# v13.net
KiCad netlist of a schematic drawn in EAGLE
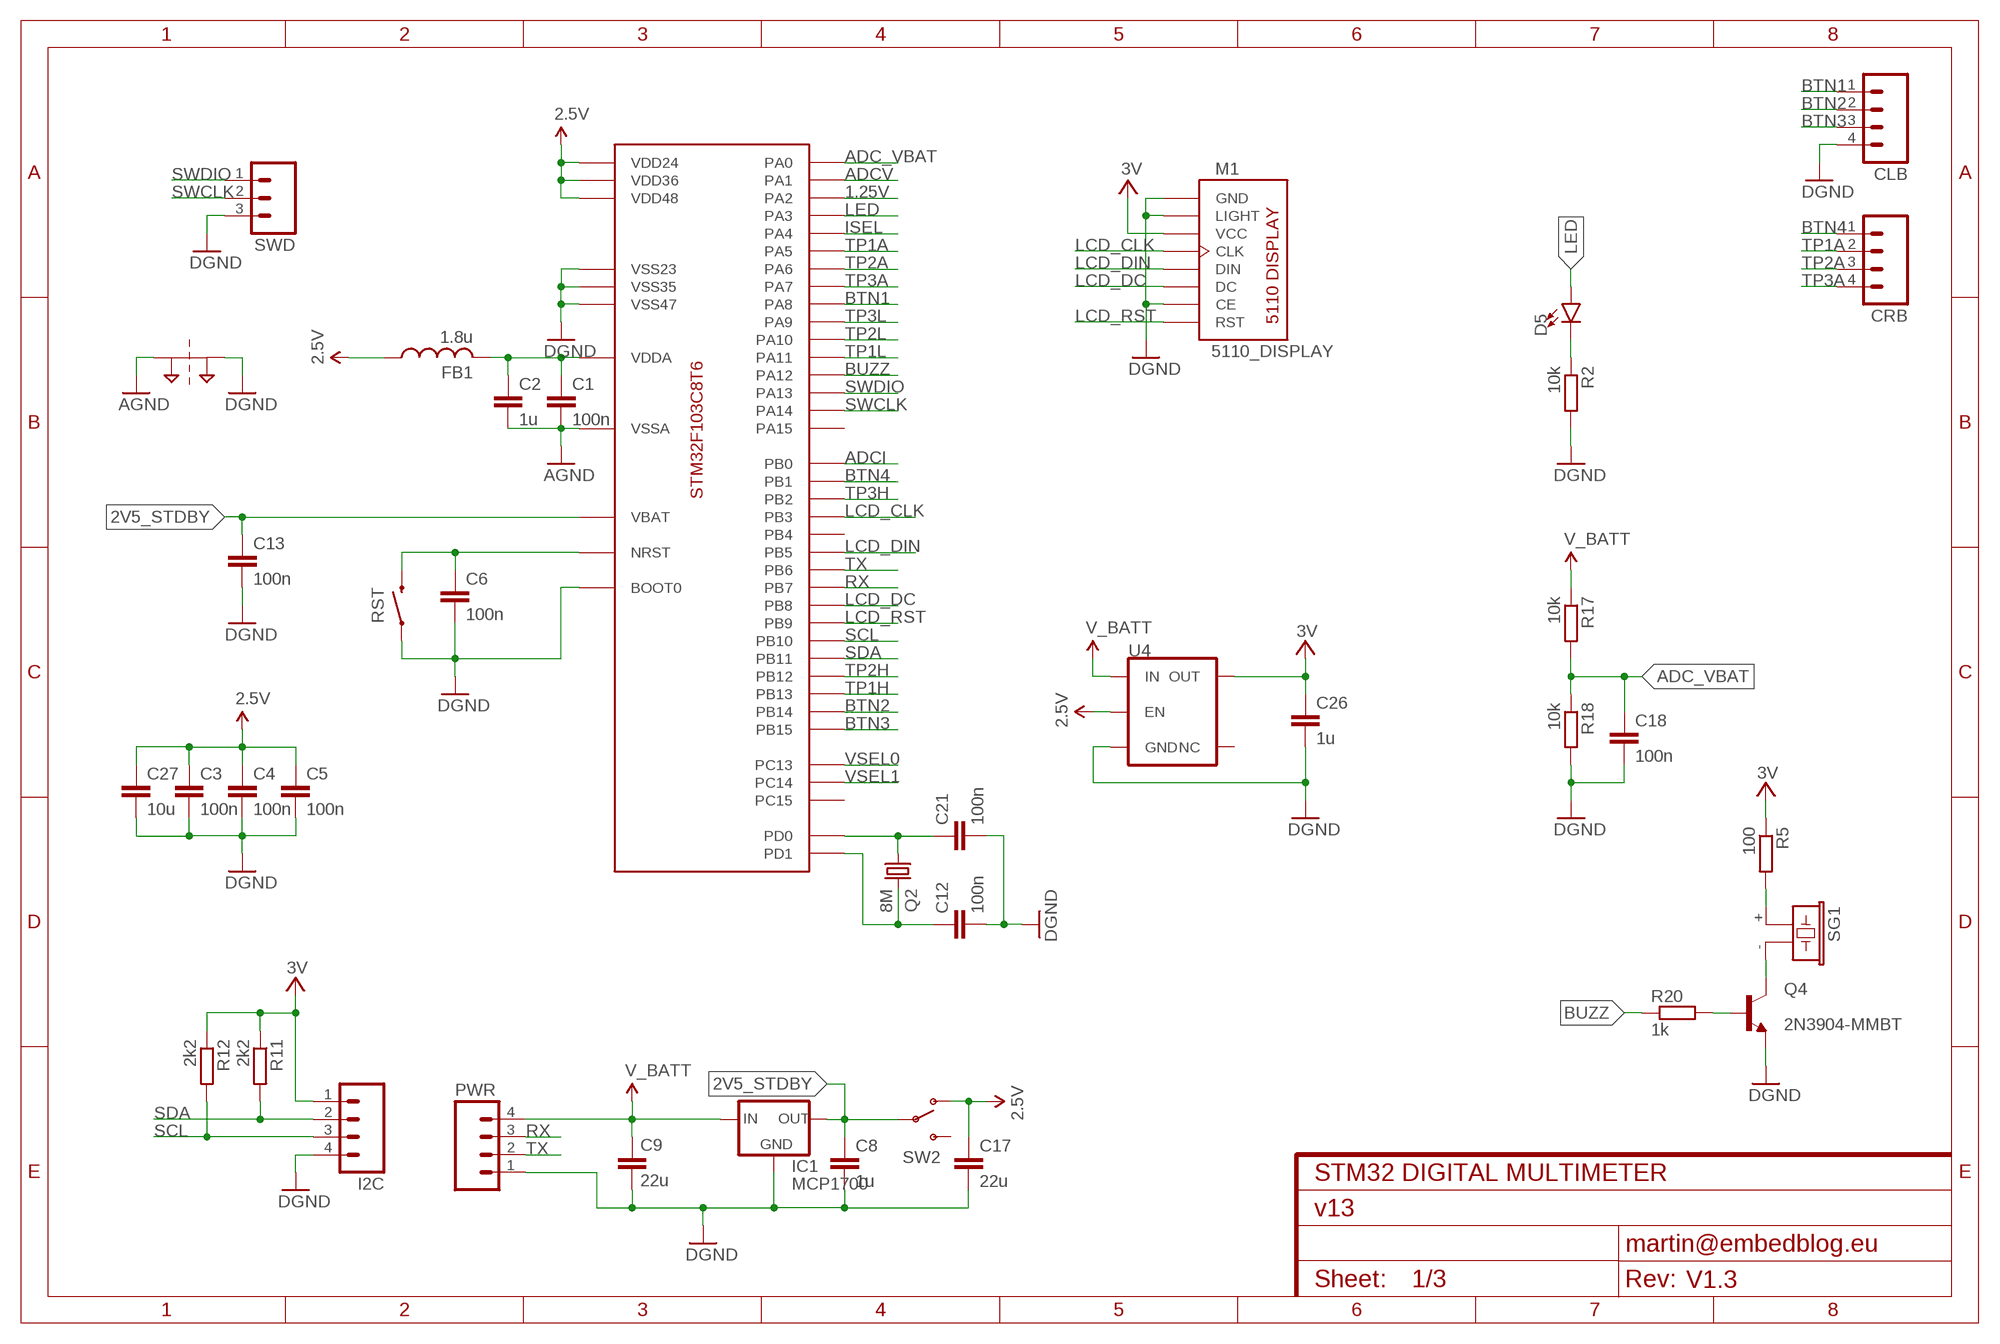
[diagram p0: schematic, sheet 1]
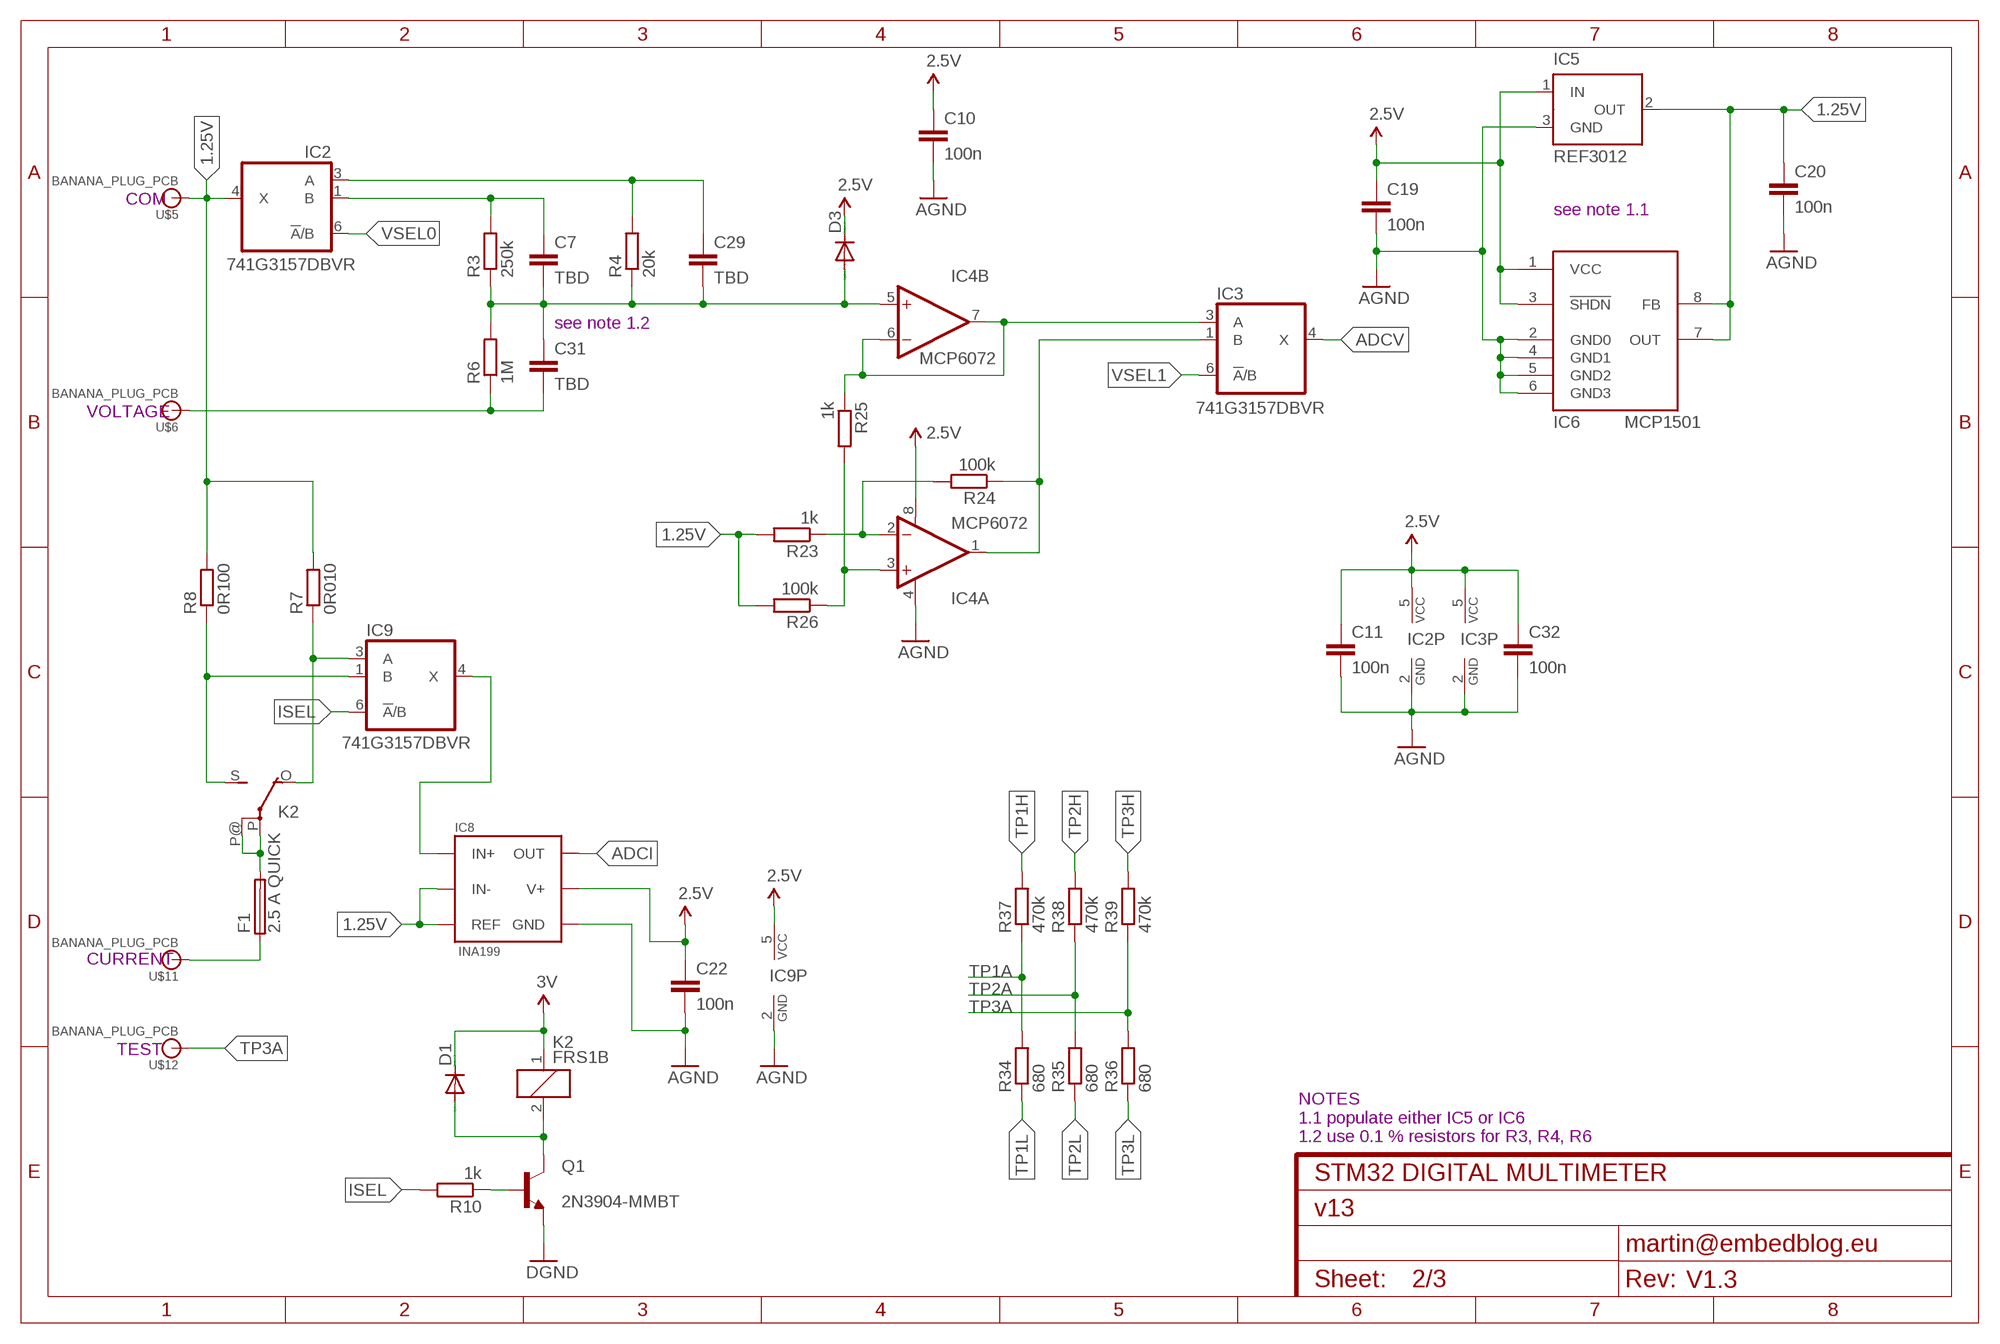
[diagram p1: schematic, sheet 2]
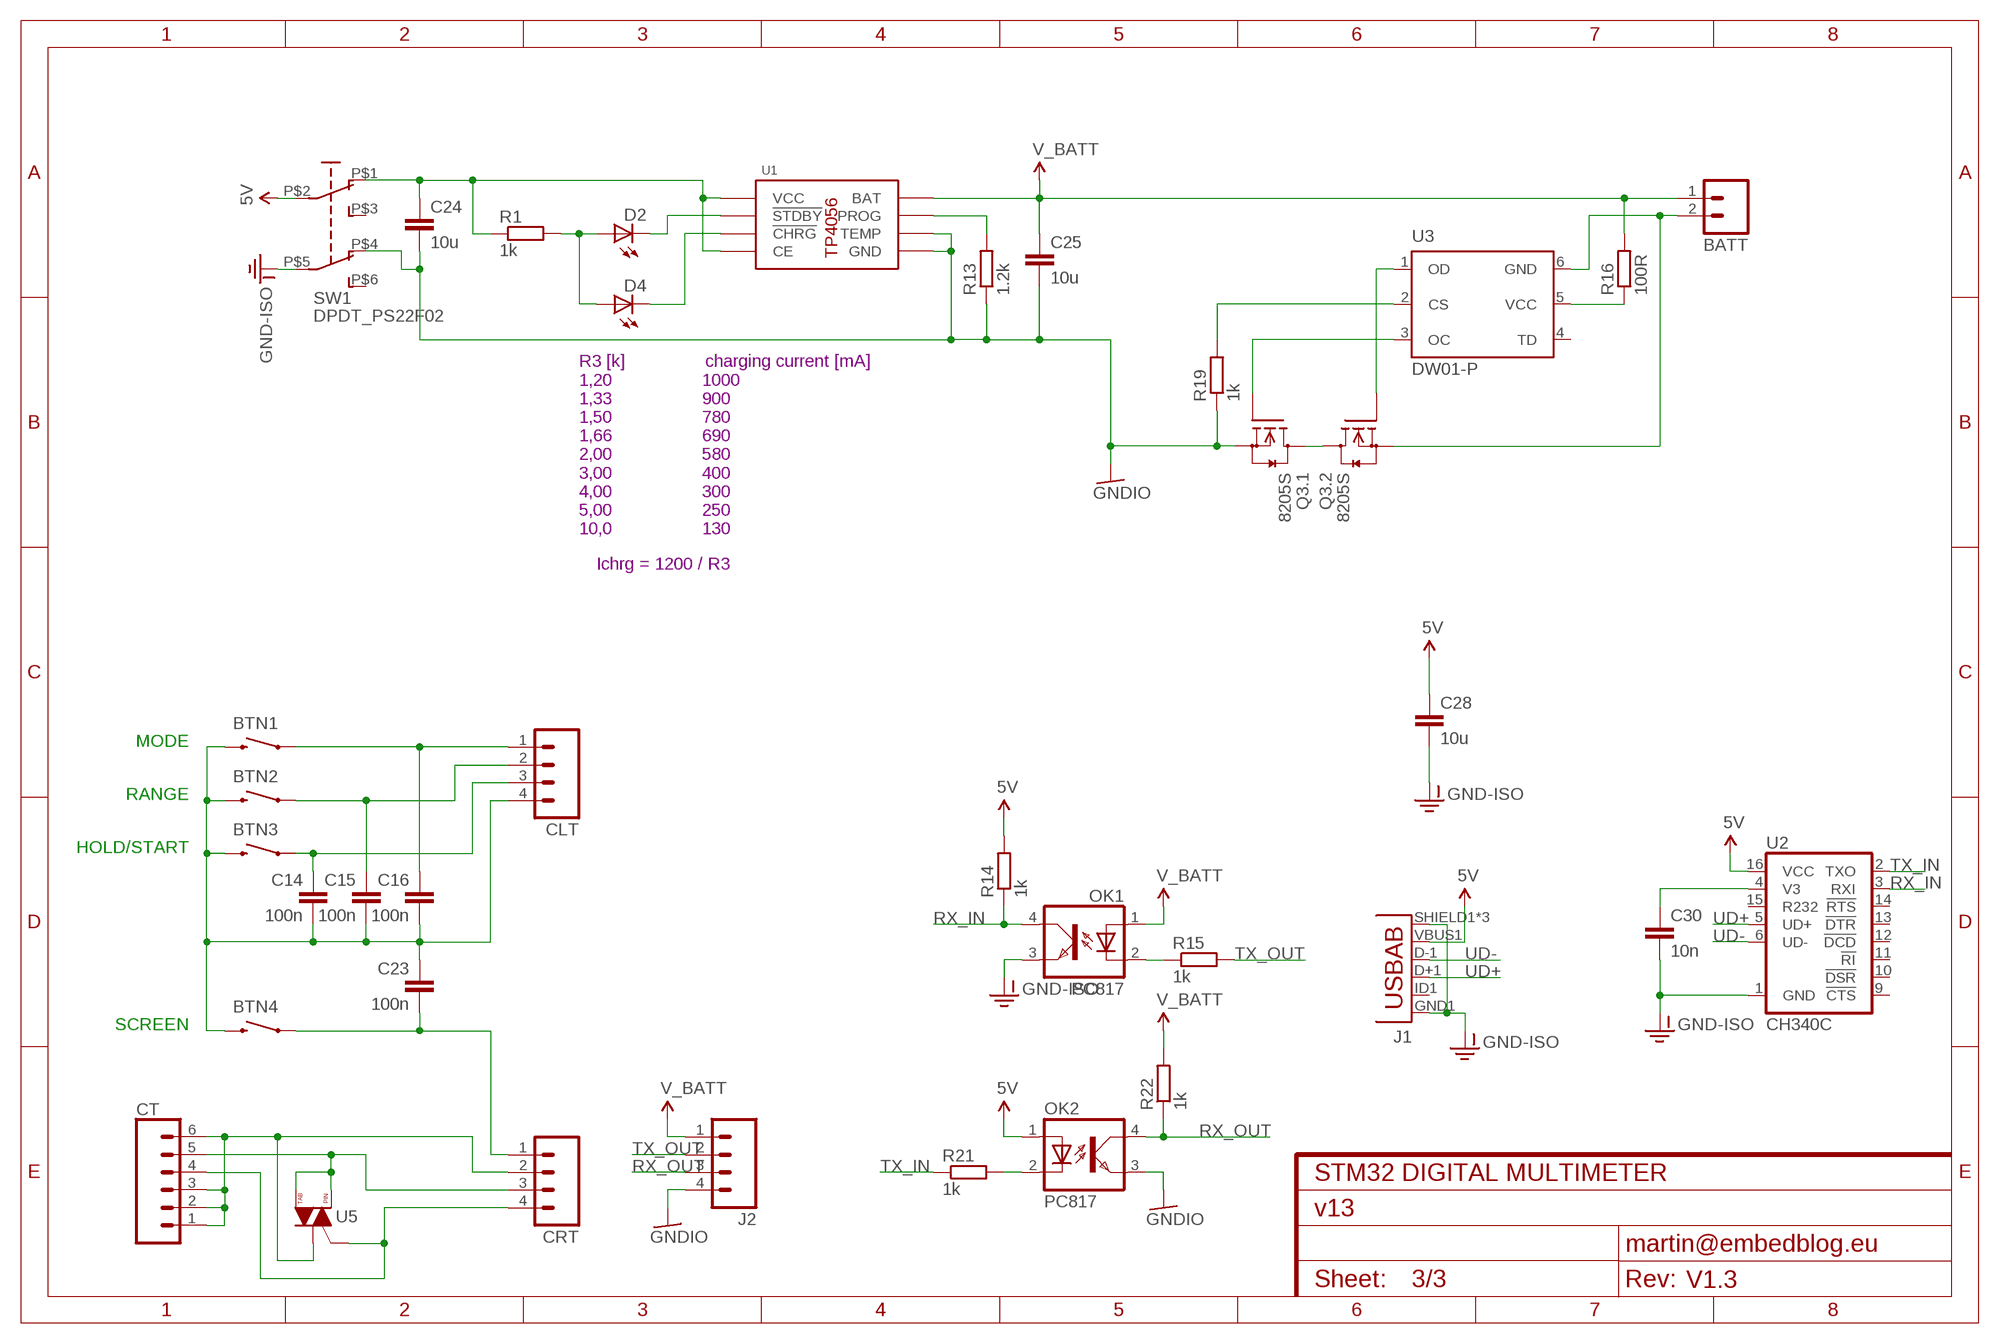
[diagram p2: schematic, sheet 3]

(export (version "E")
  (design (tool "Eeschema 10.0.6"))
  (components
    (comp (ref "C7")
      (value "TBD")
      (footprint "eagle-import:1206")
      (libsource (lib "eagle-import") (part "CAP1206"))
    )
    (comp (ref "C10")
      (value "100n")
      (footprint "eagle-import:1206")
      (libsource (lib "eagle-import") (part "CAP1206"))
    )
    (comp (ref "C11")
      (value "100n")
      (footprint "eagle-import:1206")
      (libsource (lib "eagle-import") (part "CAP1206"))
    )
    (comp (ref "C19")
      (value "100n")
      (footprint "eagle-import:C1206")
      (libsource (lib "eagle-import") (part "C-EUC1206"))
    )
    (comp (ref "C20")
      (value "100n")
      (footprint "eagle-import:C1206")
      (libsource (lib "eagle-import") (part "C-EUC1206"))
    )
    (comp (ref "C22")
      (value "100n")
      (footprint "eagle-import:1206")
      (libsource (lib "eagle-import") (part "CAP1206"))
    )
    (comp (ref "C29")
      (value "TBD")
      (footprint "eagle-import:1206")
      (libsource (lib "eagle-import") (part "CAP1206"))
    )
    (comp (ref "C31")
      (value "TBD")
      (footprint "eagle-import:1206")
      (libsource (lib "eagle-import") (part "CAP1206"))
    )
    (comp (ref "C32")
      (value "100n")
      (footprint "eagle-import:1206")
      (libsource (lib "eagle-import") (part "CAP1206"))
    )
    (comp (ref "D1")
      (value "DIODE-MINIMELF")
      (footprint "eagle-import:MINIMELF")
      (libsource (lib "eagle-import") (part "DIODE-MINIMELF"))
    )
    (comp (ref "D3")
      (value "DIODE-MINIMELF")
      (footprint "eagle-import:MINIMELF")
      (libsource (lib "eagle-import") (part "DIODE-MINIMELF"))
    )
    (comp (ref "F1")
      (value "2.5 A QUICK")
      (footprint "eagle-import:SHK20L")
      (libsource (lib "eagle-import") (part "FUSESHK20L"))
    )
    (comp (ref "IC2")
      (value "741G3157DBVR")
      (footprint "eagle-import:DBV_R-PDSO-G6")
      (libsource (lib "eagle-import") (part "741G3157DBVR"))
    )
    (comp (ref "IC3")
      (value "741G3157DBVR")
      (footprint "eagle-import:DBV_R-PDSO-G6")
      (libsource (lib "eagle-import") (part "741G3157DBVR"))
    )
    (comp (ref "IC4")
      (value "MCP6072")
      (footprint "eagle-import:SO08")
      (libsource (lib "eagle-import") (part "OPAMP-DUALU"))
    )
    (comp (ref "IC5")
      (value "REF3012")
      (footprint "eagle-import:SOT23")
      (fields (field (name "MF") "MAXIM") (field (name "MPN") "MAX6520EUR-T"))
      (libsource (lib "eagle-import") (part "MAX6520"))
    )
    (comp (ref "IC6")
      (value "MCP1501")
      (footprint "eagle-import:SO08")
      (libsource (lib "eagle-import") (part "MCP1501"))
    )
    (comp (ref "IC8")
      (value "INA199")
      (footprint "eagle-import:SC70-6")
      (libsource (lib "eagle-import") (part "INA199"))
    )
    (comp (ref "IC9")
      (value "741G3157DBVR")
      (footprint "eagle-import:DBV_R-PDSO-G6")
      (libsource (lib "eagle-import") (part "741G3157DBVR"))
    )
    (comp (ref "K2")
      (value "FRS1B")
      (footprint "eagle-import:FRS1B")
      (libsource (lib "eagle-import") (part "FRS1B"))
    )
    (comp (ref "Q1")
      (value "2N3904-MMBT")
      (footprint "eagle-import:SOT23")
      (libsource (lib "eagle-import") (part "2N3904-MMBT"))
    )
    (comp (ref "R3")
      (value "250k")
      (footprint "eagle-import:R1206")
      (libsource (lib "eagle-import") (part "R-EU_R1206"))
    )
    (comp (ref "R4")
      (value "20k")
      (footprint "eagle-import:R1206")
      (libsource (lib "eagle-import") (part "R-EU_R1206"))
    )
    (comp (ref "R6")
      (value "1M")
      (footprint "eagle-import:R1206")
      (libsource (lib "eagle-import") (part "R-EU_R1206"))
    )
    (comp (ref "R7")
      (value "0R010")
      (footprint "eagle-import:R1206")
      (libsource (lib "eagle-import") (part "R-EU_R1206"))
    )
    (comp (ref "R8")
      (value "0R100")
      (footprint "eagle-import:R1206")
      (libsource (lib "eagle-import") (part "R-EU_R1206"))
    )
    (comp (ref "R10")
      (value "1k")
      (footprint "eagle-import:R1206")
      (libsource (lib "eagle-import") (part "R-EU_R1206"))
    )
    (comp (ref "R23")
      (value "1k")
      (footprint "eagle-import:R1206")
      (libsource (lib "eagle-import") (part "R-EU_R1206"))
    )
    (comp (ref "R24")
      (value "100k")
      (footprint "eagle-import:R1206")
      (libsource (lib "eagle-import") (part "R-EU_R1206"))
    )
    (comp (ref "R25")
      (value "1k")
      (footprint "eagle-import:R1206")
      (libsource (lib "eagle-import") (part "R-EU_R1206"))
    )
    (comp (ref "R26")
      (value "100k")
      (footprint "eagle-import:R1206")
      (libsource (lib "eagle-import") (part "R-EU_R1206"))
    )
    (comp (ref "R34")
      (value "680")
      (footprint "eagle-import:R1206")
      (libsource (lib "eagle-import") (part "R-EU_R1206"))
    )
    (comp (ref "R35")
      (value "680")
      (footprint "eagle-import:R1206")
      (libsource (lib "eagle-import") (part "R-EU_R1206"))
    )
    (comp (ref "R36")
      (value "680")
      (footprint "eagle-import:R1206")
      (libsource (lib "eagle-import") (part "R-EU_R1206"))
    )
    (comp (ref "R37")
      (value "470k")
      (footprint "eagle-import:R1206")
      (libsource (lib "eagle-import") (part "R-EU_R1206"))
    )
    (comp (ref "R38")
      (value "470k")
      (footprint "eagle-import:R1206")
      (libsource (lib "eagle-import") (part "R-EU_R1206"))
    )
    (comp (ref "R39")
      (value "470k")
      (footprint "eagle-import:R1206")
      (libsource (lib "eagle-import") (part "R-EU_R1206"))
    )
    (comp (ref "U$5")
      (value "BANANA_PLUG_PCB")
      (footprint "eagle-import:BANANA_6MMHOLE")
      (libsource (lib "eagle-import") (part "BANANA_PLUG_PCB"))
    )
    (comp (ref "U$6")
      (value "BANANA_PLUG_PCB")
      (footprint "eagle-import:BANANA_6MMHOLE")
      (libsource (lib "eagle-import") (part "BANANA_PLUG_PCB"))
    )
    (comp (ref "U$11")
      (value "BANANA_PLUG_PCB")
      (footprint "eagle-import:BANANA_6MMHOLE")
      (libsource (lib "eagle-import") (part "BANANA_PLUG_PCB"))
    )
    (comp (ref "U$12")
      (value "BANANA_PLUG_PCB")
      (footprint "eagle-import:BANANA_6MMHOLE")
      (libsource (lib "eagle-import") (part "BANANA_PLUG_PCB"))
    )
    (comp (ref "BATT")
      (value "M02PTH3")
      (footprint "eagle-import:1X02_LONGPADS")
      (libsource (lib "eagle-import") (part "M02PTH3"))
    )
    (comp (ref "BTN1")
      (value "SWITCH-MOMENTARY-2PTH")
      (footprint "eagle-import:TACTILE-PTH")
      (libsource (lib "eagle-import") (part "SWITCH-MOMENTARY-2PTH"))
    )
    (comp (ref "BTN2")
      (value "SWITCH-MOMENTARY-2PTH")
      (footprint "eagle-import:TACTILE-PTH")
      (libsource (lib "eagle-import") (part "SWITCH-MOMENTARY-2PTH"))
    )
    (comp (ref "BTN3")
      (value "SWITCH-MOMENTARY-2PTH")
      (footprint "eagle-import:TACTILE-PTH")
      (libsource (lib "eagle-import") (part "SWITCH-MOMENTARY-2PTH"))
    )
    (comp (ref "BTN4")
      (value "SWITCH-MOMENTARY-2PTH")
      (footprint "eagle-import:TACTILE-PTH")
      (libsource (lib "eagle-import") (part "SWITCH-MOMENTARY-2PTH"))
    )
    (comp (ref "C14")
      (value "100n")
      (footprint "eagle-import:C1206")
      (libsource (lib "eagle-import") (part "C-EUC1206"))
    )
    (comp (ref "C15")
      (value "100n")
      (footprint "eagle-import:C1206")
      (libsource (lib "eagle-import") (part "C-EUC1206"))
    )
    (comp (ref "C16")
      (value "100n")
      (footprint "eagle-import:C1206")
      (libsource (lib "eagle-import") (part "C-EUC1206"))
    )
    (comp (ref "C23")
      (value "100n")
      (footprint "eagle-import:C1206")
      (libsource (lib "eagle-import") (part "C-EUC1206"))
    )
    (comp (ref "C24")
      (value "10u")
      (footprint "eagle-import:C1206")
      (libsource (lib "eagle-import") (part "C-EUC1206"))
    )
    (comp (ref "C25")
      (value "10u")
      (footprint "eagle-import:C1206")
      (libsource (lib "eagle-import") (part "C-EUC1206"))
    )
    (comp (ref "C28")
      (value "10u")
      (footprint "eagle-import:C1206")
      (libsource (lib "eagle-import") (part "C-EUC1206"))
    )
    (comp (ref "C30")
      (value "10n")
      (footprint "eagle-import:C1206")
      (libsource (lib "eagle-import") (part "C-EUC1206"))
    )
    (comp (ref "CLT")
      (value "M04PTH")
      (footprint "eagle-import:1X04@1")
      (libsource (lib "eagle-import") (part "M04PTH"))
    )
    (comp (ref "CRT")
      (value "M04PTH")
      (footprint "eagle-import:1X04@1")
      (libsource (lib "eagle-import") (part "M04PTH"))
    )
    (comp (ref "CT")
      (value "CONN_06NO_SILK_FEMALE_PTH")
      (footprint "eagle-import:1X06_NO_SILK")
      (libsource (lib "eagle-import") (part "CONN_06NO_SILK_FEMALE_PTH"))
    )
    (comp (ref "D2")
      (value "LEDCHIPLED_1206")
      (footprint "eagle-import:CHIPLED_1206")
      (libsource (lib "eagle-import") (part "LEDCHIPLED_1206"))
    )
    (comp (ref "D4")
      (value "LEDCHIPLED_1206")
      (footprint "eagle-import:CHIPLED_1206")
      (libsource (lib "eagle-import") (part "LEDCHIPLED_1206"))
    )
    (comp (ref "J1")
      (value "USB-ABCONN-11794")
      (footprint "eagle-import:USB-AB-MICRO-SMD_V03")
      (libsource (lib "eagle-import") (part "USB-ABCONN-11794"))
    )
    (comp (ref "J2")
      (value "M04PTH")
      (footprint "eagle-import:1X04@1")
      (libsource (lib "eagle-import") (part "M04PTH"))
    )
    (comp (ref "OK1")
      (value "PC817")
      (footprint "eagle-import:DIL04")
      (fields (field (name "MPN") "PC817X4J000F"))
      (libsource (lib "eagle-import") (part "PC817"))
    )
    (comp (ref "OK2")
      (value "PC817")
      (footprint "eagle-import:DIL04")
      (fields (field (name "MPN") "PC817X4J000F"))
      (libsource (lib "eagle-import") (part "PC817"))
    )
    (comp (ref "Q3")
      (value "8205S")
      (footprint "eagle-import:SSOT-6")
      (libsource (lib "eagle-import") (part "FDC6305N"))
    )
    (comp (ref "R1")
      (value "1k")
      (footprint "eagle-import:R1206")
      (libsource (lib "eagle-import") (part "R-EU_R1206"))
    )
    (comp (ref "R13")
      (value "1.2k")
      (footprint "eagle-import:R1206")
      (libsource (lib "eagle-import") (part "R-EU_R1206"))
    )
    (comp (ref "R14")
      (value "1k")
      (footprint "eagle-import:R1206")
      (libsource (lib "eagle-import") (part "R-EU_R1206"))
    )
    (comp (ref "R15")
      (value "1k")
      (footprint "eagle-import:R1206")
      (libsource (lib "eagle-import") (part "R-EU_R1206"))
    )
    (comp (ref "R16")
      (value "100R")
      (footprint "eagle-import:R1206")
      (libsource (lib "eagle-import") (part "R-EU_R1206"))
    )
    (comp (ref "R19")
      (value "1k")
      (footprint "eagle-import:R1206")
      (libsource (lib "eagle-import") (part "R-EU_R1206"))
    )
    (comp (ref "R21")
      (value "1k")
      (footprint "eagle-import:R1206")
      (libsource (lib "eagle-import") (part "R-EU_R1206"))
    )
    (comp (ref "R22")
      (value "1k")
      (footprint "eagle-import:R1206")
      (libsource (lib "eagle-import") (part "R-EU_R1206"))
    )
    (comp (ref "SW1")
      (value "DPDT_PS22F02")
      (footprint "eagle-import:PS22_L02_DPDT_SW")
      (libsource (lib "eagle-import") (part "DPDT_PS22F02"))
    )
    (comp (ref "U1")
      (value "TP4056")
      (footprint "eagle-import:SOP8")
      (libsource (lib "eagle-import") (part "TP4056"))
    )
    (comp (ref "U2")
      (value "CH340C")
      (footprint "eagle-import:SO016")
      (libsource (lib "eagle-import") (part "CH340C"))
    )
    (comp (ref "U3")
      (value "DW01-P")
      (footprint "eagle-import:SOT23-6L")
      (libsource (lib "eagle-import") (part "DW01-P"))
    )
    (comp (ref "U5")
      (value "TRIAC-HPSMD")
      (footprint "eagle-import:SOT223")
      (libsource (lib "eagle-import") (part "TRIAC-HPSMD"))
    )
    (comp (ref "C1")
      (value "100n")
      (footprint "eagle-import:C1206")
      (libsource (lib "eagle-import") (part "C-EUC1206"))
    )
    (comp (ref "C2")
      (value "1u")
      (footprint "eagle-import:C1206")
      (libsource (lib "eagle-import") (part "C-EUC1206"))
    )
    (comp (ref "C3")
      (value "100n")
      (footprint "eagle-import:C1206")
      (libsource (lib "eagle-import") (part "C-EUC1206"))
    )
    (comp (ref "C4")
      (value "100n")
      (footprint "eagle-import:C1206")
      (libsource (lib "eagle-import") (part "C-EUC1206"))
    )
    (comp (ref "C5")
      (value "100n")
      (footprint "eagle-import:C1206")
      (libsource (lib "eagle-import") (part "C-EUC1206"))
    )
    (comp (ref "C6")
      (value "100n")
      (footprint "eagle-import:C1206")
      (libsource (lib "eagle-import") (part "C-EUC1206"))
    )
    (comp (ref "C8")
      (value "1u")
      (footprint "eagle-import:C1206")
      (libsource (lib "eagle-import") (part "C-EUC1206"))
    )
    (comp (ref "C9")
      (value "22u")
      (footprint "eagle-import:C1206")
      (libsource (lib "eagle-import") (part "C-EUC1206"))
    )
    (comp (ref "C12")
      (value "100n")
      (footprint "eagle-import:C1206")
      (libsource (lib "eagle-import") (part "C-EUC1206"))
    )
    (comp (ref "C13")
      (value "100n")
      (footprint "eagle-import:C1206")
      (libsource (lib "eagle-import") (part "C-EUC1206"))
    )
    (comp (ref "C17")
      (value "22u")
      (footprint "eagle-import:C1206")
      (libsource (lib "eagle-import") (part "C-EUC1206"))
    )
    (comp (ref "C18")
      (value "100n")
      (footprint "eagle-import:C1206")
      (libsource (lib "eagle-import") (part "C-EUC1206"))
    )
    (comp (ref "C21")
      (value "100n")
      (footprint "eagle-import:C1206")
      (libsource (lib "eagle-import") (part "C-EUC1206"))
    )
    (comp (ref "C26")
      (value "1u")
      (footprint "eagle-import:C1206")
      (libsource (lib "eagle-import") (part "C-EUC1206"))
    )
    (comp (ref "C27")
      (value "10u")
      (footprint "eagle-import:C1206")
      (libsource (lib "eagle-import") (part "C-EUC1206"))
    )
    (comp (ref "CLB")
      (value "M04PTH")
      (footprint "eagle-import:1X04@1")
      (libsource (lib "eagle-import") (part "M04PTH"))
    )
    (comp (ref "CRB")
      (value "M04PTH")
      (footprint "eagle-import:1X04@1")
      (libsource (lib "eagle-import") (part "M04PTH"))
    )
    (comp (ref "D5")
      (value "LED1206")
      (footprint "eagle-import:LED-1206")
      (libsource (lib "eagle-import") (part "LED1206"))
    )
    (comp (ref "FB1")
      (value "1.8u")
      (footprint "eagle-import:1206")
      (libsource (lib "eagle-import") (part "FERRITE-BEADC"))
    )
    (comp (ref "I2C")
      (value "M04PTH")
      (footprint "eagle-import:1X04@1")
      (libsource (lib "eagle-import") (part "M04PTH"))
    )
    (comp (ref "IC1")
      (value "MCP1700")
      (footprint "eagle-import:SOT23")
      (libsource (lib "eagle-import") (part "XC63FPM"))
    )
    (comp (ref "M1")
      (value "5110_DISPLAY")
      (footprint "eagle-import:5110_LAYOUT")
      (libsource (lib "eagle-import") (part "5110_DISPLAY"))
    )
    (comp (ref "PWR")
      (value "M04PTH")
      (footprint "eagle-import:1X04@1")
      (libsource (lib "eagle-import") (part "M04PTH"))
    )
    (comp (ref "Q2")
      (value "8M")
      (footprint "eagle-import:HC49U-V")
      (libsource (lib "eagle-import") (part "CRYSTALHC49U-V"))
    )
    (comp (ref "Q4")
      (value "2N3904-MMBT")
      (footprint "eagle-import:SOT23")
      (libsource (lib "eagle-import") (part "2N3904-MMBT"))
    )
    (comp (ref "R2")
      (value "10k")
      (footprint "eagle-import:R1206")
      (libsource (lib "eagle-import") (part "R-EU_R1206"))
    )
    (comp (ref "R5")
      (value "100")
      (footprint "eagle-import:R1206")
      (libsource (lib "eagle-import") (part "R-EU_R1206"))
    )
    (comp (ref "R11")
      (value "2k2")
      (footprint "eagle-import:R1206")
      (libsource (lib "eagle-import") (part "R-EU_R1206"))
    )
    (comp (ref "R12")
      (value "2k2")
      (footprint "eagle-import:R1206")
      (libsource (lib "eagle-import") (part "R-EU_R1206"))
    )
    (comp (ref "R17")
      (value "10k")
      (footprint "eagle-import:R1206")
      (libsource (lib "eagle-import") (part "R-EU_R1206"))
    )
    (comp (ref "R18")
      (value "10k")
      (footprint "eagle-import:R1206")
      (libsource (lib "eagle-import") (part "R-EU_R1206"))
    )
    (comp (ref "R20")
      (value "1k")
      (footprint "eagle-import:R1206")
      (libsource (lib "eagle-import") (part "R-EU_R1206"))
    )
    (comp (ref "RST")
      (value "SWITCH-MOMENTARY-2SMD")
      (footprint "eagle-import:TACTILE-SWITCH-SMD")
      (libsource (lib "eagle-import") (part "SWITCH-MOMENTARY-2SMD"))
    )
    (comp (ref "SG1")
      (value "F/CM12P")
      (footprint "eagle-import:F_CM12P")
      (libsource (lib "eagle-import") (part "F/CM12P"))
    )
    (comp (ref "SJ1")
      (value "2PT_GND_TIE")
      (footprint "eagle-import:2PT_GND_TIE")
      (libsource (lib "eagle-import") (part "2PT_GND_TIE"))
    )
    (comp (ref "SW2")
      (value "SK-12D07")
      (footprint "eagle-import:SK12SWITCH")
      (libsource (lib "eagle-import") (part "SK-12D07"))
    )
    (comp (ref "SWD")
      (value "M03PTH")
      (footprint "eagle-import:1X03")
      (libsource (lib "eagle-import") (part "M03PTH"))
    )
    (comp (ref "U$1")
      (value "STM32F103C8T6")
      (footprint "eagle-import:TQFP-48")
      (libsource (lib "eagle-import") (part "STM32F103C8T6"))
    )
    (comp (ref "U4")
      (value "3.3V")
      (footprint "eagle-import:SOT23-5")
      (libsource (lib "eagle-import") (part "V_REG_AP2112K-3.3V"))
    )
  )
  (nets
    (net (code "1") (name "1.25V") (class "Default")
      (node (ref "C20") (pin "1") (pinfunction "1_1") (pintype "passive"))
      (node (ref "IC2") (pin "4") (pinfunction "X_4") (pintype "bidirectional"))
      (node (ref "IC5") (pin "2") (pinfunction "OUT_2") (pintype "output"))
      (node (ref "IC6") (pin "7") (pinfunction "OUT_7") (pintype "bidirectional"))
      (node (ref "IC6") (pin "8") (pinfunction "FB_8") (pintype "bidirectional"))
      (node (ref "IC8") (pin "1") (pinfunction "REF_1") (pintype "bidirectional"))
      (node (ref "IC8") (pin "5") (pinfunction "IN-_5") (pintype "bidirectional"))
      (node (ref "R23") (pin "2") (pinfunction "2_2") (pintype "passive"))
      (node (ref "R26") (pin "2") (pinfunction "2_2") (pintype "passive"))
      (node (ref "R7") (pin "2") (pinfunction "2_2") (pintype "passive"))
      (node (ref "R8") (pin "2") (pinfunction "2_2") (pintype "passive"))
      (node (ref "U$1") (pin "12") (pinfunction "PA2_12") (pintype "bidirectional"))
      (node (ref "U$5") (pin "P$1") (pinfunction "1_P$1") (pintype "passive"))
    )
    (net (code "2") (name "2.5V") (class "Default")
      (node (ref "C10") (pin "1") (pinfunction "1_1") (pintype "passive"))
      (node (ref "C11") (pin "1") (pinfunction "1_1") (pintype "passive"))
      (node (ref "C17") (pin "1") (pinfunction "1_1") (pintype "passive"))
      (node (ref "C19") (pin "1") (pinfunction "1_1") (pintype "passive"))
      (node (ref "C22") (pin "1") (pinfunction "1_1") (pintype "passive"))
      (node (ref "C27") (pin "1") (pinfunction "1_1") (pintype "passive"))
      (node (ref "C3") (pin "1") (pinfunction "1_1") (pintype "passive"))
      (node (ref "C32") (pin "1") (pinfunction "1_1") (pintype "passive"))
      (node (ref "C4") (pin "1") (pinfunction "1_1") (pintype "passive"))
      (node (ref "C5") (pin "1") (pinfunction "1_1") (pintype "passive"))
      (node (ref "D3") (pin "C") (pinfunction "C_C") (pintype "passive"))
      (node (ref "FB1") (pin "1") (pinfunction "1_1") (pintype "passive"))
      (node (ref "IC2") (pin "5") (pinfunction "VCC_5") (pintype "power_in"))
      (node (ref "IC3") (pin "5") (pinfunction "VCC_5") (pintype "power_in"))
      (node (ref "IC4") (pin "8") (pinfunction "V+_8") (pintype "power_in"))
      (node (ref "IC5") (pin "1") (pinfunction "IN_1") (pintype "input"))
      (node (ref "IC6") (pin "1") (pinfunction "VCC_1") (pintype "bidirectional"))
      (node (ref "IC6") (pin "3") (pinfunction "~{SHDN}_3") (pintype "bidirectional"))
      (node (ref "IC8") (pin "3") (pinfunction "V+_3") (pintype "bidirectional"))
      (node (ref "IC9") (pin "5") (pinfunction "VCC_5") (pintype "power_in"))
      (node (ref "SW2") (pin "IN") (pinfunction "O_IN") (pintype "passive"))
      (node (ref "U$1") (pin "24") (pinfunction "VDD24_24") (pintype "input"))
      (node (ref "U$1") (pin "36") (pinfunction "VDD36_36") (pintype "input"))
      (node (ref "U$1") (pin "48") (pinfunction "VDD48_48") (pintype "input"))
      (node (ref "U4") (pin "3") (pinfunction "EN_3") (pintype "input"))
    )
    (net (code "3") (name "2V5_STDBY") (class "Default")
      (node (ref "C13") (pin "1") (pinfunction "1_1") (pintype "passive"))
      (node (ref "C8") (pin "1") (pinfunction "1_1") (pintype "passive"))
      (node (ref "IC1") (pin "2") (pinfunction "OUT_2") (pintype "passive"))
      (node (ref "SW2") (pin "P1") (pinfunction "P_P1") (pintype "passive"))
      (node (ref "U$1") (pin "1") (pinfunction "VBAT_1") (pintype "input"))
    )
    (net (code "4") (name "3V") (class "Default")
      (node (ref "C26") (pin "1") (pinfunction "1_1") (pintype "passive"))
      (node (ref "D1") (pin "C") (pinfunction "C_C") (pintype "passive"))
      (node (ref "I2C") (pin "1") (pinfunction "1_1") (pintype "passive"))
      (node (ref "K2") (pin "1") (pinfunction "1_1") (pintype "passive"))
      (node (ref "M1") (pin "VCC") (pinfunction "VCC_VCC") (pintype "bidirectional"))
      (node (ref "R11") (pin "1") (pinfunction "1_1") (pintype "passive"))
      (node (ref "R12") (pin "1") (pinfunction "1_1") (pintype "passive"))
      (node (ref "R5") (pin "1") (pinfunction "1_1") (pintype "passive"))
      (node (ref "U4") (pin "5") (pinfunction "OUT_5") (pintype "passive"))
    )
    (net (code "5") (name "5V") (class "Default")
      (node (ref "C28") (pin "1") (pinfunction "1_1") (pintype "passive"))
      (node (ref "J1") (pin "VBUS1") (pinfunction "VBUS_VBUS1") (pintype "bidirectional"))
      (node (ref "OK2") (pin "1") (pinfunction "A_1") (pintype "passive"))
      (node (ref "R14") (pin "2") (pinfunction "2_2") (pintype "passive"))
      (node (ref "SW1") (pin "P$2") (pinfunction "P_P$2") (pintype "passive"))
      (node (ref "U2") (pin "16") (pinfunction "VCC_16") (pintype "bidirectional"))
    )
    (net (code "6") (name "ADCI") (class "Default")
      (node (ref "IC8") (pin "6") (pinfunction "OUT_6") (pintype "bidirectional"))
      (node (ref "U$1") (pin "18") (pinfunction "PB0_18") (pintype "bidirectional"))
    )
    (net (code "7") (name "ADCV") (class "Default")
      (node (ref "IC3") (pin "4") (pinfunction "X_4") (pintype "bidirectional"))
      (node (ref "U$1") (pin "11") (pinfunction "PA1_11") (pintype "bidirectional"))
    )
    (net (code "8") (name "ADC_VBAT") (class "Default")
      (node (ref "C18") (pin "1") (pinfunction "1_1") (pintype "passive"))
      (node (ref "R17") (pin "2") (pinfunction "2_2") (pintype "passive"))
      (node (ref "R18") (pin "1") (pinfunction "1_1") (pintype "passive"))
      (node (ref "U$1") (pin "10") (pinfunction "PA0_10") (pintype "bidirectional"))
    )
    (net (code "9") (name "AGND") (class "Default")
      (node (ref "C1") (pin "2") (pinfunction "2_2") (pintype "passive"))
      (node (ref "C10") (pin "2") (pinfunction "2_2") (pintype "passive"))
      (node (ref "C11") (pin "2") (pinfunction "2_2") (pintype "passive"))
      (node (ref "C19") (pin "2") (pinfunction "2_2") (pintype "passive"))
      (node (ref "C2") (pin "2") (pinfunction "2_2") (pintype "passive"))
      (node (ref "C20") (pin "2") (pinfunction "2_2") (pintype "passive"))
      (node (ref "C22") (pin "2") (pinfunction "2_2") (pintype "passive"))
      (node (ref "C32") (pin "2") (pinfunction "2_2") (pintype "passive"))
      (node (ref "IC2") (pin "2") (pinfunction "GND_2") (pintype "power_in"))
      (node (ref "IC3") (pin "2") (pinfunction "GND_2") (pintype "power_in"))
      (node (ref "IC4") (pin "4") (pinfunction "V-_4") (pintype "power_in"))
      (node (ref "IC5") (pin "3") (pinfunction "GND_3") (pintype "power_in"))
      (node (ref "IC6") (pin "2") (pinfunction "GND0_2") (pintype "bidirectional"))
      (node (ref "IC6") (pin "4") (pinfunction "GND1_4") (pintype "bidirectional"))
      (node (ref "IC6") (pin "5") (pinfunction "GND2_5") (pintype "bidirectional"))
      (node (ref "IC6") (pin "6") (pinfunction "GND3_6") (pintype "bidirectional"))
      (node (ref "IC8") (pin "2") (pinfunction "GND_2") (pintype "bidirectional"))
      (node (ref "IC9") (pin "2") (pinfunction "GND_2") (pintype "power_in"))
      (node (ref "SJ1") (pin "P$1") (pinfunction "P$1_P$1") (pintype "bidirectional"))
      (node (ref "U$1") (pin "8") (pinfunction "VSSA_8") (pintype "input"))
    )
    (net (code "10") (name "BTN1") (class "Default")
      (node (ref "CLB") (pin "1") (pinfunction "1_1") (pintype "passive"))
      (node (ref "U$1") (pin "29") (pinfunction "PA8_29") (pintype "bidirectional"))
    )
    (net (code "11") (name "BTN2") (class "Default")
      (node (ref "CLB") (pin "2") (pinfunction "2_2") (pintype "passive"))
      (node (ref "U$1") (pin "27") (pinfunction "PB14_27") (pintype "bidirectional"))
    )
    (net (code "12") (name "BTN3") (class "Default")
      (node (ref "CLB") (pin "3") (pinfunction "3_3") (pintype "passive"))
      (node (ref "U$1") (pin "28") (pinfunction "PB15_28") (pintype "bidirectional"))
    )
    (net (code "13") (name "BTN4") (class "Default")
      (node (ref "CRB") (pin "1") (pinfunction "1_1") (pintype "passive"))
      (node (ref "U$1") (pin "19") (pinfunction "PB1_19") (pintype "bidirectional"))
    )
    (net (code "14") (name "BUZZ") (class "Default")
      (node (ref "R20") (pin "1") (pinfunction "1_1") (pintype "passive"))
      (node (ref "U$1") (pin "33") (pinfunction "PA12_33") (pintype "bidirectional"))
    )
    (net (code "15") (name "GND") (class "Default")
      (node (ref "C12") (pin "2") (pinfunction "2_2") (pintype "passive"))
      (node (ref "C13") (pin "2") (pinfunction "2_2") (pintype "passive"))
      (node (ref "C17") (pin "2") (pinfunction "2_2") (pintype "passive"))
      (node (ref "C18") (pin "2") (pinfunction "2_2") (pintype "passive"))
      (node (ref "C21") (pin "2") (pinfunction "2_2") (pintype "passive"))
      (node (ref "C26") (pin "2") (pinfunction "2_2") (pintype "passive"))
      (node (ref "C27") (pin "2") (pinfunction "2_2") (pintype "passive"))
      (node (ref "C3") (pin "2") (pinfunction "2_2") (pintype "passive"))
      (node (ref "C4") (pin "2") (pinfunction "2_2") (pintype "passive"))
      (node (ref "C5") (pin "2") (pinfunction "2_2") (pintype "passive"))
      (node (ref "C6") (pin "2") (pinfunction "2_2") (pintype "passive"))
      (node (ref "C8") (pin "2") (pinfunction "2_2") (pintype "passive"))
      (node (ref "C9") (pin "2") (pinfunction "2_2") (pintype "passive"))
      (node (ref "CLB") (pin "4") (pinfunction "4_4") (pintype "passive"))
      (node (ref "I2C") (pin "4") (pinfunction "4_4") (pintype "passive"))
      (node (ref "IC1") (pin "1") (pinfunction "GND_1") (pintype "input"))
      (node (ref "M1") (pin "CE") (pinfunction "CE_CE") (pintype "bidirectional"))
      (node (ref "M1") (pin "GND") (pinfunction "GND_GND") (pintype "bidirectional"))
      (node (ref "M1") (pin "LIGHT") (pinfunction "LIGHT_LIGHT") (pintype "bidirectional"))
      (node (ref "PWR") (pin "1") (pinfunction "1_1") (pintype "passive"))
      (node (ref "Q1") (pin "2") (pinfunction "E_2") (pintype "passive"))
      (node (ref "Q4") (pin "2") (pinfunction "E_2") (pintype "passive"))
      (node (ref "R18") (pin "2") (pinfunction "2_2") (pintype "passive"))
      (node (ref "R2") (pin "2") (pinfunction "2_2") (pintype "passive"))
      (node (ref "RST") (pin "1") (pinfunction "1_1") (pintype "passive"))
      (node (ref "SJ1") (pin "P$2") (pinfunction "P$2_P$2") (pintype "bidirectional"))
      (node (ref "SWD") (pin "3") (pinfunction "3_3") (pintype "passive"))
      (node (ref "U$1") (pin "23") (pinfunction "VSS23_23") (pintype "input"))
      (node (ref "U$1") (pin "35") (pinfunction "VSS35_35") (pintype "input"))
      (node (ref "U$1") (pin "44") (pinfunction "BOOT0_44") (pintype "input"))
      (node (ref "U$1") (pin "47") (pinfunction "VSS47_47") (pintype "input"))
      (node (ref "U4") (pin "2") (pinfunction "GND_2") (pintype "input"))
    )
    (net (code "16") (name "GND-ISO") (class "Default")
      (node (ref "C28") (pin "2") (pinfunction "2_2") (pintype "passive"))
      (node (ref "C30") (pin "2") (pinfunction "2_2") (pintype "passive"))
      (node (ref "J1") (pin "GND1") (pinfunction "GND_GND1") (pintype "bidirectional"))
      (node (ref "J1") (pin "SHIELD1") (pinfunction "SHIELD_SHIELD1") (pintype "bidirectional"))
      (node (ref "J1") (pin "SHIELD2") (pinfunction "SHIELD_SHIELD2") (pintype "bidirectional"))
      (node (ref "J1") (pin "SHIELD3") (pinfunction "SHIELD_SHIELD3") (pintype "bidirectional"))
      (node (ref "OK1") (pin "3") (pinfunction "EMIT_3") (pintype "passive"))
      (node (ref "SW1") (pin "P$5") (pinfunction "P1_P$5") (pintype "passive"))
      (node (ref "U2") (pin "1") (pinfunction "GND_1") (pintype "bidirectional"))
    )
    (net (code "17") (name "GNDIO") (class "Default")
      (node (ref "C24") (pin "2") (pinfunction "2_2") (pintype "passive"))
      (node (ref "C25") (pin "2") (pinfunction "2_2") (pintype "passive"))
      (node (ref "J2") (pin "4") (pinfunction "4_4") (pintype "passive"))
      (node (ref "OK2") (pin "3") (pinfunction "EMIT_3") (pintype "passive"))
      (node (ref "Q3") (pin "5") (pinfunction "S_5") (pintype "passive"))
      (node (ref "R13") (pin "1") (pinfunction "1_1") (pintype "passive"))
      (node (ref "R19") (pin "1") (pinfunction "1_1") (pintype "passive"))
      (node (ref "SW1") (pin "P$4") (pinfunction "O1_P$4") (pintype "passive"))
      (node (ref "U1") (pin "1") (pinfunction "TEMP_1") (pintype "bidirectional"))
      (node (ref "U1") (pin "3") (pinfunction "GND_3") (pintype "bidirectional"))
    )
    (net (code "18") (name "ISEL") (class "Default")
      (node (ref "IC9") (pin "6") (pinfunction "~{A}/B_6") (pintype "input"))
      (node (ref "R10") (pin "2") (pinfunction "2_2") (pintype "passive"))
      (node (ref "U$1") (pin "14") (pinfunction "PA4_14") (pintype "bidirectional"))
    )
    (net (code "19") (name "LCD_CLK") (class "Default")
      (node (ref "M1") (pin "CLK") (pinfunction "CLK_CLK") (pintype "bidirectional"))
      (node (ref "U$1") (pin "39") (pinfunction "PB3_39") (pintype "bidirectional"))
    )
    (net (code "20") (name "LCD_DC") (class "Default")
      (node (ref "M1") (pin "DC") (pinfunction "DC_DC") (pintype "bidirectional"))
      (node (ref "U$1") (pin "45") (pinfunction "PB8_45") (pintype "bidirectional"))
    )
    (net (code "21") (name "LCD_DIN") (class "Default")
      (node (ref "M1") (pin "DIN") (pinfunction "DIN_DIN") (pintype "bidirectional"))
      (node (ref "U$1") (pin "41") (pinfunction "PB5_41") (pintype "bidirectional"))
    )
    (net (code "22") (name "LCD_RST") (class "Default")
      (node (ref "M1") (pin "RST") (pinfunction "RST_RST") (pintype "bidirectional"))
      (node (ref "U$1") (pin "46") (pinfunction "PB9_46") (pintype "bidirectional"))
    )
    (net (code "23") (name "LED") (class "Default")
      (node (ref "D5") (pin "A") (pinfunction "A_A") (pintype "passive"))
      (node (ref "U$1") (pin "13") (pinfunction "PA3_13") (pintype "bidirectional"))
    )
    (net (code "24") (name "Net-(BTN1-2)") (class "Default")
      (node (ref "BTN1") (pin "3") (pinfunction "2_3") (pintype "passive"))
      (node (ref "BTN2") (pin "3") (pinfunction "2_3") (pintype "passive"))
      (node (ref "BTN3") (pin "3") (pinfunction "2_3") (pintype "passive"))
      (node (ref "BTN4") (pin "3") (pinfunction "2_3") (pintype "passive"))
      (node (ref "C14") (pin "2") (pinfunction "2_2") (pintype "passive"))
      (node (ref "C15") (pin "2") (pinfunction "2_2") (pintype "passive"))
      (node (ref "C16") (pin "2") (pinfunction "2_2") (pintype "passive"))
      (node (ref "C23") (pin "1") (pinfunction "1_1") (pintype "passive"))
      (node (ref "CLT") (pin "4") (pinfunction "4_4") (pintype "passive"))
    )
    (net (code "25") (name "Net-(BTN1-Pad1)") (class "Default")
      (node (ref "BTN1") (pin "1") (pinfunction "1_1") (pintype "passive"))
      (node (ref "C16") (pin "1") (pinfunction "1_1") (pintype "passive"))
      (node (ref "CLT") (pin "1") (pinfunction "1_1") (pintype "passive"))
    )
    (net (code "26") (name "Net-(BTN2-Pad1)") (class "Default")
      (node (ref "BTN2") (pin "1") (pinfunction "1_1") (pintype "passive"))
      (node (ref "C15") (pin "1") (pinfunction "1_1") (pintype "passive"))
      (node (ref "CLT") (pin "2") (pinfunction "2_2") (pintype "passive"))
    )
    (net (code "27") (name "Net-(BTN3-Pad1)") (class "Default")
      (node (ref "BTN3") (pin "1") (pinfunction "1_1") (pintype "passive"))
      (node (ref "C14") (pin "1") (pinfunction "1_1") (pintype "passive"))
      (node (ref "CLT") (pin "3") (pinfunction "3_3") (pintype "passive"))
    )
    (net (code "28") (name "Net-(BTN4-Pad1)") (class "Default")
      (node (ref "BTN4") (pin "1") (pinfunction "1_1") (pintype "passive"))
      (node (ref "C23") (pin "2") (pinfunction "2_2") (pintype "passive"))
      (node (ref "CRT") (pin "1") (pinfunction "1_1") (pintype "passive"))
    )
    (net (code "29") (name "Net-(CRT-Pad3)") (class "Default")
      (node (ref "CRT") (pin "3") (pinfunction "3_3") (pintype "passive"))
      (node (ref "CT") (pin "5") (pinfunction "5_5") (pintype "passive"))
      (node (ref "U5") (pin "2") (pinfunction "T2_2") (pintype "passive"))
      (node (ref "U5") (pin "4") (pinfunction "T2_4") (pintype "passive"))
    )
    (net (code "30") (name "Net-(D2-PadA)") (class "Default")
      (node (ref "D2") (pin "A") (pinfunction "A_A") (pintype "passive"))
      (node (ref "D4") (pin "A") (pinfunction "A_A") (pintype "passive"))
      (node (ref "R1") (pin "2") (pinfunction "2_2") (pintype "passive"))
    )
    (net (code "31") (name "Net-(D5-PadC)") (class "Default")
      (node (ref "D5") (pin "C") (pinfunction "C_C") (pintype "passive"))
      (node (ref "R2") (pin "1") (pinfunction "1_1") (pintype "passive"))
    )
    (net (code "32") (name "Net-(F1-1)") (class "Default")
      (node (ref "F1") (pin "1A") (pinfunction "1_1A") (pintype "passive"))
      (node (ref "U$11") (pin "P$1") (pinfunction "1_P$1") (pintype "passive"))
    )
    (net (code "33") (name "Net-(F1-2)") (class "Default")
      (node (ref "F1") (pin "2A") (pinfunction "2_2A") (pintype "passive"))
      (node (ref "K2") (pin "P") (pinfunction "P_P") (pintype "passive"))
      (node (ref "K2") (pin "P@") (pinfunction "P_P@") (pintype "passive"))
    )
    (net (code "34") (name "Net-(IC2A-A)") (class "Default")
      (node (ref "C29") (pin "1") (pinfunction "1_1") (pintype "passive"))
      (node (ref "IC2") (pin "3") (pinfunction "A_3") (pintype "bidirectional"))
      (node (ref "R4") (pin "2") (pinfunction "2_2") (pintype "passive"))
    )
    (net (code "35") (name "Net-(IC2A-B)") (class "Default")
      (node (ref "C7") (pin "1") (pinfunction "1_1") (pintype "passive"))
      (node (ref "IC2") (pin "1") (pinfunction "B_1") (pintype "bidirectional"))
      (node (ref "R3") (pin "2") (pinfunction "2_2") (pintype "passive"))
    )
    (net (code "36") (name "Net-(IC3A-A)") (class "Default")
      (node (ref "IC3") (pin "3") (pinfunction "A_3") (pintype "bidirectional"))
      (node (ref "IC4") (pin "6") (pinfunction "-IN_6") (pintype "input"))
      (node (ref "IC4") (pin "7") (pinfunction "OUT_7") (pintype "output"))
      (node (ref "R25") (pin "1") (pinfunction "1_1") (pintype "passive"))
    )
    (net (code "37") (name "Net-(IC3A-B)") (class "Default")
      (node (ref "IC3") (pin "1") (pinfunction "B_1") (pintype "bidirectional"))
      (node (ref "IC4") (pin "1") (pinfunction "OUT_1") (pintype "output"))
      (node (ref "R24") (pin "1") (pinfunction "1_1") (pintype "passive"))
    )
    (net (code "38") (name "Net-(IC4A-+IN)") (class "Default")
      (node (ref "IC4") (pin "3") (pinfunction "+IN_3") (pintype "input"))
      (node (ref "R25") (pin "2") (pinfunction "2_2") (pintype "passive"))
      (node (ref "R26") (pin "1") (pinfunction "1_1") (pintype "passive"))
    )
    (net (code "39") (name "Net-(IC4A--IN)") (class "Default")
      (node (ref "IC4") (pin "2") (pinfunction "-IN_2") (pintype "input"))
      (node (ref "R23") (pin "1") (pinfunction "1_1") (pintype "passive"))
      (node (ref "R24") (pin "2") (pinfunction "2_2") (pintype "passive"))
    )
    (net (code "40") (name "Net-(IC4B-+IN)") (class "Default")
      (node (ref "C29") (pin "2") (pinfunction "2_2") (pintype "passive"))
      (node (ref "C31") (pin "1") (pinfunction "1_1") (pintype "passive"))
      (node (ref "C7") (pin "2") (pinfunction "2_2") (pintype "passive"))
      (node (ref "D3") (pin "A") (pinfunction "A_A") (pintype "passive"))
      (node (ref "IC4") (pin "5") (pinfunction "+IN_5") (pintype "input"))
      (node (ref "R3") (pin "1") (pinfunction "1_1") (pintype "passive"))
      (node (ref "R4") (pin "1") (pinfunction "1_1") (pintype "passive"))
      (node (ref "R6") (pin "2") (pinfunction "2_2") (pintype "passive"))
    )
    (net (code "41") (name "Net-(IC8-IN+)") (class "Default")
      (node (ref "IC8") (pin "4") (pinfunction "IN+_4") (pintype "bidirectional"))
      (node (ref "IC9") (pin "4") (pinfunction "X_4") (pintype "bidirectional"))
    )
    (net (code "42") (name "Net-(IC9A-A)") (class "Default")
      (node (ref "IC9") (pin "3") (pinfunction "A_3") (pintype "bidirectional"))
      (node (ref "K2") (pin "O") (pinfunction "O_O") (pintype "passive"))
      (node (ref "R7") (pin "1") (pinfunction "1_1") (pintype "passive"))
    )
    (net (code "43") (name "Net-(IC9A-B)") (class "Default")
      (node (ref "IC9") (pin "1") (pinfunction "B_1") (pintype "bidirectional"))
      (node (ref "K2") (pin "S") (pinfunction "S_S") (pintype "passive"))
      (node (ref "R8") (pin "1") (pinfunction "1_1") (pintype "passive"))
    )
    (net (code "44") (name "Net-(OK1-C)") (class "Default")
      (node (ref "OK1") (pin "2") (pinfunction "C_2") (pintype "passive"))
      (node (ref "R15") (pin "1") (pinfunction "1_1") (pintype "passive"))
    )
    (net (code "45") (name "Net-(OK2-C)") (class "Default")
      (node (ref "OK2") (pin "2") (pinfunction "C_2") (pintype "passive"))
      (node (ref "R21") (pin "2") (pinfunction "2_2") (pintype "passive"))
    )
    (net (code "46") (name "Net-(Q1-B)") (class "Default")
      (node (ref "Q1") (pin "1") (pinfunction "B_1") (pintype "passive"))
      (node (ref "R10") (pin "1") (pinfunction "1_1") (pintype "passive"))
    )
    (net (code "47") (name "Net-(Q1-C)") (class "Default")
      (node (ref "D1") (pin "A") (pinfunction "A_A") (pintype "passive"))
      (node (ref "K2") (pin "2") (pinfunction "2_2") (pintype "passive"))
      (node (ref "Q1") (pin "3") (pinfunction "C_3") (pintype "passive"))
    )
    (net (code "48") (name "Net-(Q3A-D)") (class "Default")
      (node (ref "Q3") (pin "4") (pinfunction "D_4") (pintype "passive"))
      (node (ref "Q3") (pin "6") (pinfunction "D_6") (pintype "passive"))
    )
    (net (code "49") (name "Net-(Q3A-G)") (class "Default")
      (node (ref "Q3") (pin "1") (pinfunction "G_1") (pintype "passive"))
      (node (ref "U3") (pin "3") (pinfunction "OC_3") (pintype "power_in"))
    )
    (net (code "50") (name "Net-(Q3B-G)") (class "Default")
      (node (ref "Q3") (pin "3") (pinfunction "G_3") (pintype "passive"))
      (node (ref "U3") (pin "1") (pinfunction "OD_1") (pintype "power_in"))
    )
    (net (code "51") (name "Net-(Q3B-S)") (class "Default")
      (node (ref "BATT") (pin "2") (pinfunction "2_2") (pintype "passive"))
      (node (ref "Q3") (pin "2") (pinfunction "S_2") (pintype "passive"))
      (node (ref "U3") (pin "6") (pinfunction "GND_6") (pintype "output"))
    )
    (net (code "52") (name "Net-(Q4-B)") (class "Default")
      (node (ref "Q4") (pin "1") (pinfunction "B_1") (pintype "passive"))
      (node (ref "R20") (pin "2") (pinfunction "2_2") (pintype "passive"))
    )
    (net (code "53") (name "Net-(Q4-C)") (class "Default")
      (node (ref "Q4") (pin "3") (pinfunction "C_3") (pintype "passive"))
      (node (ref "SG1") (pin "-") (pinfunction "2_-") (pintype "passive"))
    )
    (net (code "54") (name "Net-(RST-2)") (class "Default")
      (node (ref "C6") (pin "1") (pinfunction "1_1") (pintype "passive"))
      (node (ref "RST") (pin "3") (pinfunction "2_3") (pintype "passive"))
      (node (ref "U$1") (pin "7") (pinfunction "NRST_7") (pintype "input"))
    )
    (net (code "55") (name "Net-(SG1-1)") (class "Default")
      (node (ref "R5") (pin "2") (pinfunction "2_2") (pintype "passive"))
      (node (ref "SG1") (pin "+") (pinfunction "1_+") (pintype "passive"))
    )
    (net (code "56") (name "Net-(SW1-O)") (class "Default")
      (node (ref "C24") (pin "1") (pinfunction "1_1") (pintype "passive"))
      (node (ref "R1") (pin "1") (pinfunction "1_1") (pintype "passive"))
      (node (ref "SW1") (pin "P$1") (pinfunction "O_P$1") (pintype "passive"))
      (node (ref "U1") (pin "4") (pinfunction "VCC_4") (pintype "bidirectional"))
      (node (ref "U1") (pin "8") (pinfunction "CE_8") (pintype "bidirectional"))
    )
    (net (code "57") (name "Net-(U$1-PD0)") (class "Default")
      (node (ref "C21") (pin "1") (pinfunction "1_1") (pintype "passive"))
      (node (ref "Q2") (pin "1") (pinfunction "1_1") (pintype "passive"))
      (node (ref "U$1") (pin "5") (pinfunction "PD0_5") (pintype "bidirectional"))
    )
    (net (code "58") (name "Net-(U$1-PD1)") (class "Default")
      (node (ref "C12") (pin "1") (pinfunction "1_1") (pintype "passive"))
      (node (ref "Q2") (pin "2") (pinfunction "2_2") (pintype "passive"))
      (node (ref "U$1") (pin "6") (pinfunction "PD1_6") (pintype "bidirectional"))
    )
    (net (code "59") (name "Net-(U$1-VDDA)") (class "Default")
      (node (ref "C1") (pin "1") (pinfunction "1_1") (pintype "passive"))
      (node (ref "C2") (pin "1") (pinfunction "1_1") (pintype "passive"))
      (node (ref "FB1") (pin "2") (pinfunction "2_2") (pintype "passive"))
      (node (ref "U$1") (pin "9") (pinfunction "VDDA_9") (pintype "input"))
    )
    (net (code "60") (name "Net-(U$6-1)") (class "Default")
      (node (ref "C31") (pin "2") (pinfunction "2_2") (pintype "passive"))
      (node (ref "R6") (pin "1") (pinfunction "1_1") (pintype "passive"))
      (node (ref "U$6") (pin "P$1") (pinfunction "1_P$1") (pintype "passive"))
    )
    (net (code "61") (name "Net-(U1-PROG)") (class "Default")
      (node (ref "R13") (pin "2") (pinfunction "2_2") (pintype "passive"))
      (node (ref "U1") (pin "2") (pinfunction "PROG_2") (pintype "bidirectional"))
    )
    (net (code "62") (name "Net-(U1-~{CHRG})") (class "Default")
      (node (ref "D4") (pin "C") (pinfunction "C_C") (pintype "passive"))
      (node (ref "U1") (pin "7") (pinfunction "~{CHRG}_7") (pintype "bidirectional"))
    )
    (net (code "63") (name "Net-(U1-~{STDBY})") (class "Default")
      (node (ref "D2") (pin "C") (pinfunction "C_C") (pintype "passive"))
      (node (ref "U1") (pin "6") (pinfunction "~{STDBY}_6") (pintype "bidirectional"))
    )
    (net (code "64") (name "Net-(U2-V3)") (class "Default")
      (node (ref "C30") (pin "1") (pinfunction "1_1") (pintype "passive"))
      (node (ref "U2") (pin "4") (pinfunction "V3_4") (pintype "bidirectional"))
    )
    (net (code "65") (name "Net-(U3-CS)") (class "Default")
      (node (ref "R19") (pin "2") (pinfunction "2_2") (pintype "passive"))
      (node (ref "U3") (pin "2") (pinfunction "CS_2") (pintype "input"))
    )
    (net (code "66") (name "Net-(U3-VCC)") (class "Default")
      (node (ref "R16") (pin "1") (pinfunction "1_1") (pintype "passive"))
      (node (ref "U3") (pin "5") (pinfunction "VCC_5") (pintype "input"))
    )
    (net (code "67") (name "Net-(U5-G)") (class "Default")
      (node (ref "CRT") (pin "4") (pinfunction "4_4") (pintype "passive"))
      (node (ref "CT") (pin "4") (pinfunction "4_4") (pintype "passive"))
      (node (ref "U5") (pin "3") (pinfunction "G_3") (pintype "bidirectional"))
    )
    (net (code "68") (name "Net-(U5-T1)") (class "Default")
      (node (ref "CRT") (pin "2") (pinfunction "2_2") (pintype "passive"))
      (node (ref "CT") (pin "1") (pinfunction "1_1") (pintype "passive"))
      (node (ref "CT") (pin "2") (pinfunction "2_2") (pintype "passive"))
      (node (ref "CT") (pin "3") (pinfunction "3_3") (pintype "passive"))
      (node (ref "CT") (pin "6") (pinfunction "6_6") (pintype "passive"))
      (node (ref "U5") (pin "1") (pinfunction "T1_1") (pintype "bidirectional"))
    )
    (net (code "69") (name "RX") (class "Default")
      (node (ref "PWR") (pin "3") (pinfunction "3_3") (pintype "passive"))
      (node (ref "U$1") (pin "43") (pinfunction "PB7_43") (pintype "bidirectional"))
    )
    (net (code "70") (name "RX_IN") (class "Default")
      (node (ref "OK1") (pin "4") (pinfunction "COL_4") (pintype "passive"))
      (node (ref "R14") (pin "1") (pinfunction "1_1") (pintype "passive"))
      (node (ref "U2") (pin "3") (pinfunction "RXI_3") (pintype "bidirectional"))
    )
    (net (code "71") (name "RX_OUT") (class "Default")
      (node (ref "J2") (pin "3") (pinfunction "3_3") (pintype "passive"))
      (node (ref "OK2") (pin "4") (pinfunction "COL_4") (pintype "passive"))
      (node (ref "R22") (pin "1") (pinfunction "1_1") (pintype "passive"))
    )
    (net (code "72") (name "SCL") (class "Default")
      (node (ref "I2C") (pin "3") (pinfunction "3_3") (pintype "passive"))
      (node (ref "R12") (pin "2") (pinfunction "2_2") (pintype "passive"))
      (node (ref "U$1") (pin "21") (pinfunction "PB10_21") (pintype "bidirectional"))
    )
    (net (code "73") (name "SDA") (class "Default")
      (node (ref "I2C") (pin "2") (pinfunction "2_2") (pintype "passive"))
      (node (ref "R11") (pin "2") (pinfunction "2_2") (pintype "passive"))
      (node (ref "U$1") (pin "22") (pinfunction "PB11_22") (pintype "bidirectional"))
    )
    (net (code "74") (name "SWCLK") (class "Default")
      (node (ref "SWD") (pin "2") (pinfunction "2_2") (pintype "passive"))
      (node (ref "U$1") (pin "37") (pinfunction "PA14_37") (pintype "bidirectional"))
    )
    (net (code "75") (name "SWDIO") (class "Default")
      (node (ref "SWD") (pin "1") (pinfunction "1_1") (pintype "passive"))
      (node (ref "U$1") (pin "34") (pinfunction "PA13_34") (pintype "bidirectional"))
    )
    (net (code "76") (name "TP1A") (class "Default")
      (node (ref "CRB") (pin "2") (pinfunction "2_2") (pintype "passive"))
      (node (ref "R34") (pin "2") (pinfunction "2_2") (pintype "passive"))
      (node (ref "R37") (pin "1") (pinfunction "1_1") (pintype "passive"))
      (node (ref "U$1") (pin "15") (pinfunction "PA5_15") (pintype "bidirectional"))
    )
    (net (code "77") (name "TP1H") (class "Default")
      (node (ref "R37") (pin "2") (pinfunction "2_2") (pintype "passive"))
      (node (ref "U$1") (pin "26") (pinfunction "PB13_26") (pintype "bidirectional"))
    )
    (net (code "78") (name "TP1L") (class "Default")
      (node (ref "R34") (pin "1") (pinfunction "1_1") (pintype "passive"))
      (node (ref "U$1") (pin "32") (pinfunction "PA11_32") (pintype "bidirectional"))
    )
    (net (code "79") (name "TP2A") (class "Default")
      (node (ref "CRB") (pin "3") (pinfunction "3_3") (pintype "passive"))
      (node (ref "R35") (pin "2") (pinfunction "2_2") (pintype "passive"))
      (node (ref "R38") (pin "1") (pinfunction "1_1") (pintype "passive"))
      (node (ref "U$1") (pin "16") (pinfunction "PA6_16") (pintype "bidirectional"))
    )
    (net (code "80") (name "TP2H") (class "Default")
      (node (ref "R38") (pin "2") (pinfunction "2_2") (pintype "passive"))
      (node (ref "U$1") (pin "25") (pinfunction "PB12_25") (pintype "bidirectional"))
    )
    (net (code "81") (name "TP2L") (class "Default")
      (node (ref "R35") (pin "1") (pinfunction "1_1") (pintype "passive"))
      (node (ref "U$1") (pin "31") (pinfunction "PA10_31") (pintype "bidirectional"))
    )
    (net (code "82") (name "TP3A") (class "Default")
      (node (ref "CRB") (pin "4") (pinfunction "4_4") (pintype "passive"))
      (node (ref "R36") (pin "2") (pinfunction "2_2") (pintype "passive"))
      (node (ref "R39") (pin "1") (pinfunction "1_1") (pintype "passive"))
      (node (ref "U$1") (pin "17") (pinfunction "PA7_17") (pintype "bidirectional"))
      (node (ref "U$12") (pin "P$1") (pinfunction "1_P$1") (pintype "passive"))
    )
    (net (code "83") (name "TP3H") (class "Default")
      (node (ref "R39") (pin "2") (pinfunction "2_2") (pintype "passive"))
      (node (ref "U$1") (pin "20") (pinfunction "PB2_20") (pintype "bidirectional"))
    )
    (net (code "84") (name "TP3L") (class "Default")
      (node (ref "R36") (pin "1") (pinfunction "1_1") (pintype "passive"))
      (node (ref "U$1") (pin "30") (pinfunction "PA9_30") (pintype "bidirectional"))
    )
    (net (code "85") (name "TX") (class "Default")
      (node (ref "PWR") (pin "2") (pinfunction "2_2") (pintype "passive"))
      (node (ref "U$1") (pin "42") (pinfunction "PB6_42") (pintype "bidirectional"))
    )
    (net (code "86") (name "TX_IN") (class "Default")
      (node (ref "R21") (pin "1") (pinfunction "1_1") (pintype "passive"))
      (node (ref "U2") (pin "2") (pinfunction "TXO_2") (pintype "bidirectional"))
    )
    (net (code "87") (name "TX_OUT") (class "Default")
      (node (ref "J2") (pin "2") (pinfunction "2_2") (pintype "passive"))
      (node (ref "R15") (pin "2") (pinfunction "2_2") (pintype "passive"))
    )
    (net (code "88") (name "UD+") (class "Default")
      (node (ref "J1") (pin "D+1") (pinfunction "D+_D+1") (pintype "bidirectional"))
      (node (ref "U2") (pin "5") (pinfunction "UD+_5") (pintype "bidirectional"))
    )
    (net (code "89") (name "UD-") (class "Default")
      (node (ref "J1") (pin "D-1") (pinfunction "D-_D-1") (pintype "bidirectional"))
      (node (ref "U2") (pin "6") (pinfunction "UD-_6") (pintype "bidirectional"))
    )
    (net (code "90") (name "VSEL0") (class "Default")
      (node (ref "IC2") (pin "6") (pinfunction "~{A}/B_6") (pintype "input"))
      (node (ref "U$1") (pin "2") (pinfunction "PC13_2") (pintype "bidirectional"))
    )
    (net (code "91") (name "VSEL1") (class "Default")
      (node (ref "IC3") (pin "6") (pinfunction "~{A}/B_6") (pintype "input"))
      (node (ref "U$1") (pin "3") (pinfunction "PC14_3") (pintype "bidirectional"))
    )
    (net (code "92") (name "V_BATT") (class "Default")
      (node (ref "BATT") (pin "1") (pinfunction "1_1") (pintype "passive"))
      (node (ref "C25") (pin "1") (pinfunction "1_1") (pintype "passive"))
      (node (ref "C9") (pin "1") (pinfunction "1_1") (pintype "passive"))
      (node (ref "IC1") (pin "3") (pinfunction "IN_3") (pintype "input"))
      (node (ref "J2") (pin "1") (pinfunction "1_1") (pintype "passive"))
      (node (ref "OK1") (pin "1") (pinfunction "A_1") (pintype "passive"))
      (node (ref "PWR") (pin "4") (pinfunction "4_4") (pintype "passive"))
      (node (ref "R16") (pin "2") (pinfunction "2_2") (pintype "passive"))
      (node (ref "R17") (pin "1") (pinfunction "1_1") (pintype "passive"))
      (node (ref "R22") (pin "2") (pinfunction "2_2") (pintype "passive"))
      (node (ref "U1") (pin "5") (pinfunction "BAT_5") (pintype "bidirectional"))
      (node (ref "U4") (pin "1") (pinfunction "IN_1") (pintype "input"))
    )
    (net (code "93") (name "unconnected-(J1-USBID-PadID1)") (class "Default")
      (node (ref "J1") (pin "ID1") (pinfunction "USBID_ID1") (pintype "bidirectional"))
    )
    (net (code "94") (name "unconnected-(SW1-S-PadP$3)") (class "Default")
      (node (ref "SW1") (pin "P$3") (pinfunction "S_P$3") (pintype "passive"))
    )
    (net (code "95") (name "unconnected-(SW1-S1-PadP$6)") (class "Default")
      (node (ref "SW1") (pin "P$6") (pinfunction "S1_P$6") (pintype "passive"))
    )
    (net (code "96") (name "unconnected-(SW2-S-PadP2)") (class "Default")
      (node (ref "SW2") (pin "P2") (pinfunction "S_P2") (pintype "passive"))
    )
    (net (code "97") (name "unconnected-(U$1-PA15-Pad38)") (class "Default")
      (node (ref "U$1") (pin "38") (pinfunction "PA15_38") (pintype "bidirectional"))
    )
    (net (code "98") (name "unconnected-(U$1-PB4-Pad40)") (class "Default")
      (node (ref "U$1") (pin "40") (pinfunction "PB4_40") (pintype "bidirectional"))
    )
    (net (code "99") (name "unconnected-(U$1-PC15-Pad4)") (class "Default")
      (node (ref "U$1") (pin "4") (pinfunction "PC15_4") (pintype "bidirectional"))
    )
    (net (code "100") (name "unconnected-(U2-R232-Pad15)") (class "Default")
      (node (ref "U2") (pin "15") (pinfunction "R232_15") (pintype "bidirectional"))
    )
    (net (code "101") (name "unconnected-(U2-~{CTS}-Pad9)") (class "Default")
      (node (ref "U2") (pin "9") (pinfunction "~{CTS}_9") (pintype "bidirectional"))
    )
    (net (code "102") (name "unconnected-(U2-~{DCD}-Pad12)") (class "Default")
      (node (ref "U2") (pin "12") (pinfunction "~{DCD}_12") (pintype "bidirectional"))
    )
    (net (code "103") (name "unconnected-(U2-~{DSR}-Pad10)") (class "Default")
      (node (ref "U2") (pin "10") (pinfunction "~{DSR}_10") (pintype "bidirectional"))
    )
    (net (code "104") (name "unconnected-(U2-~{DTR}-Pad13)") (class "Default")
      (node (ref "U2") (pin "13") (pinfunction "~{DTR}_13") (pintype "bidirectional"))
    )
    (net (code "105") (name "unconnected-(U2-~{RI}-Pad11)") (class "Default")
      (node (ref "U2") (pin "11") (pinfunction "~{RI}_11") (pintype "bidirectional"))
    )
    (net (code "106") (name "unconnected-(U2-~{RTS}-Pad14)") (class "Default")
      (node (ref "U2") (pin "14") (pinfunction "~{RTS}_14") (pintype "bidirectional"))
    )
    (net (code "107") (name "unconnected-(U3-TD-Pad4)") (class "Default")
      (node (ref "U3") (pin "4") (pinfunction "TD_4") (pintype "output"))
    )
    (net (code "108") (name "unconnected-(U4-NC-Pad4)") (class "Default")
      (node (ref "U4") (pin "4") (pinfunction "NC_4") (pintype "no_connect"))
    )
  )
)
